# 32pinromtoflash.net
KiCad netlist of a schematic drawn in EAGLE
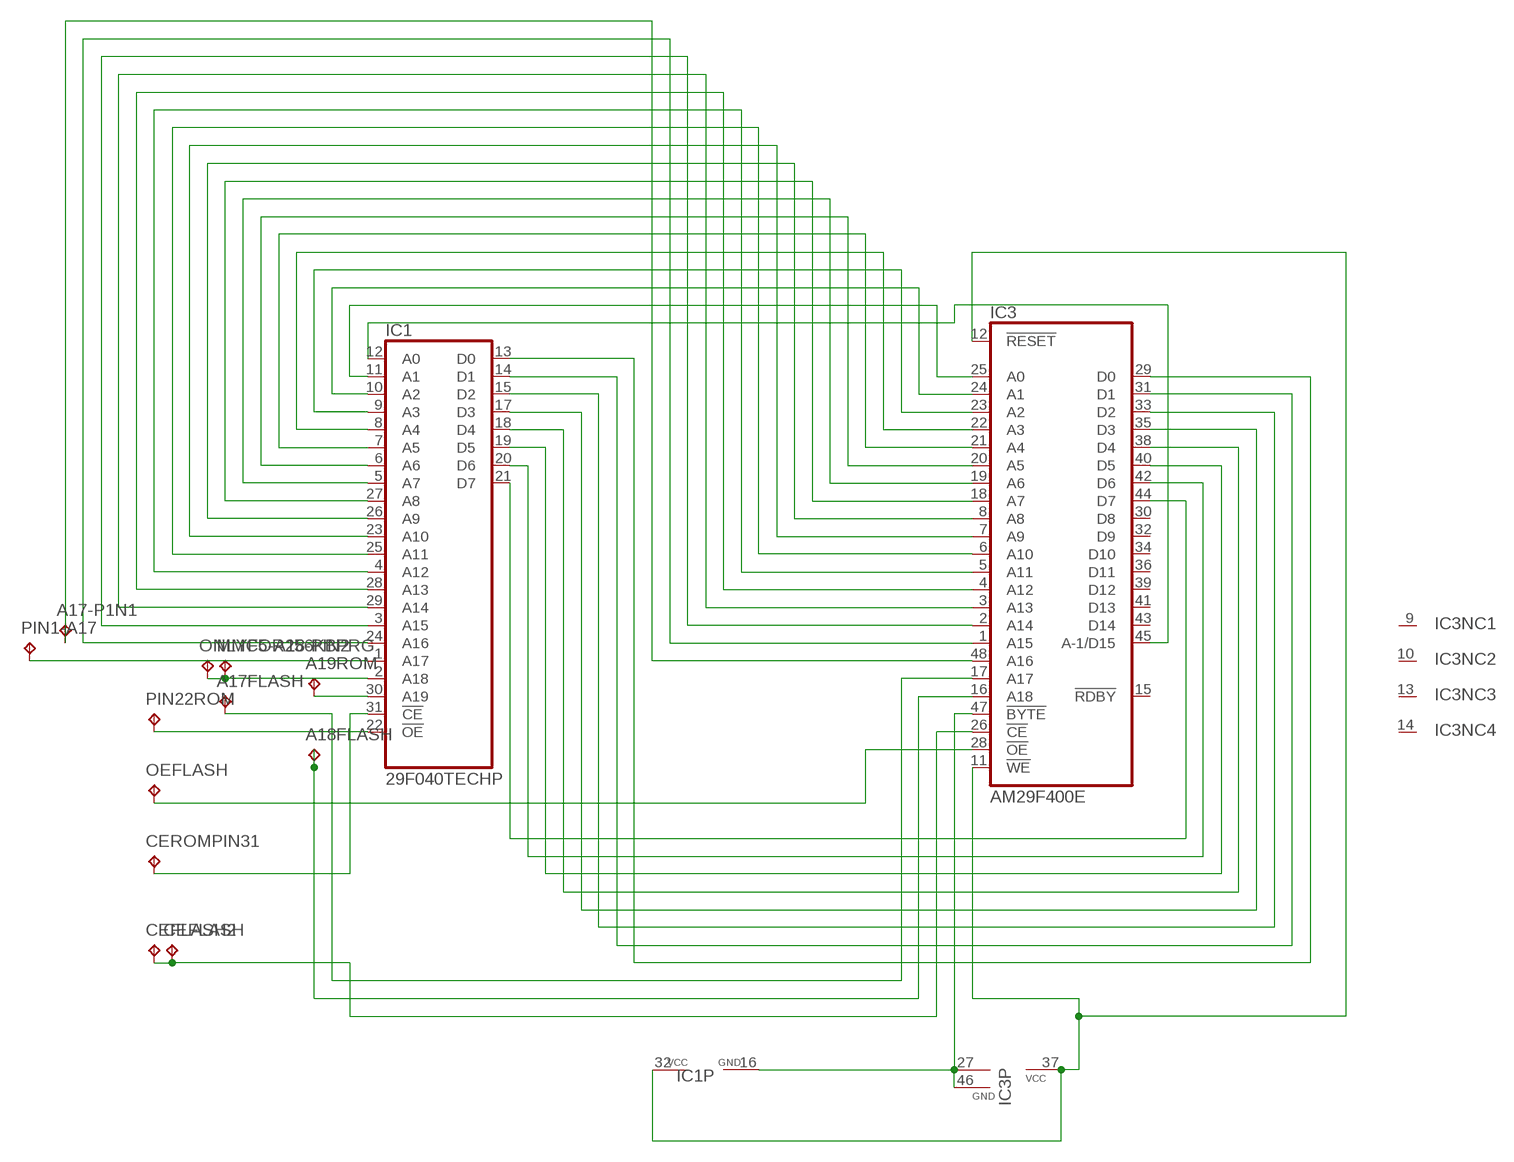
[diagram p0: schematic, sheet 1]

(export (version "E")
  (design (tool "Eeschema 10.0.6"))
  (components
    (comp (ref "A17-P1N1")
      (value "TPTP07SQ")
      (footprint "eagle-import:TP07SQ")
      (libsource (lib "eagle-import") (part "TPTP07SQ"))
    )
    (comp (ref "A17FLASH")
      (value "TPTP07SQ")
      (footprint "eagle-import:TP07SQ")
      (libsource (lib "eagle-import") (part "TPTP07SQ"))
    )
    (comp (ref "A18FLASH")
      (value "TPTP07SQ")
      (footprint "eagle-import:TP07SQ")
      (libsource (lib "eagle-import") (part "TPTP07SQ"))
    )
    (comp (ref "A19ROM")
      (value "TPTP07SQ")
      (footprint "eagle-import:TP07SQ")
      (libsource (lib "eagle-import") (part "TPTP07SQ"))
    )
    (comp (ref "CEFLASH")
      (value "TPTP07SQ")
      (footprint "eagle-import:TP07SQ")
      (libsource (lib "eagle-import") (part "TPTP07SQ"))
    )
    (comp (ref "CEFLASH2")
      (value "TPTP07SQ")
      (footprint "eagle-import:TP07SQ")
      (libsource (lib "eagle-import") (part "TPTP07SQ"))
    )
    (comp (ref "CEROMPIN31")
      (value "TPTP07SQ")
      (footprint "eagle-import:TP07SQ")
      (libsource (lib "eagle-import") (part "TPTP07SQ"))
    )
    (comp (ref "IC1")
      (value "29F040TECHP")
      (footprint "eagle-import:DIL32-3")
      (libsource (lib "eagle-import") (part "29F040PTECH"))
    )
    (comp (ref "IC3")
      (value "AM29F400E")
      (footprint "eagle-import:TSOP48")
      (libsource (lib "eagle-import") (part "AM29F400E"))
    )
    (comp (ref "MMC5-A18-PIN2")
      (value "TPTP07SQ")
      (footprint "eagle-import:TP07SQ")
      (libsource (lib "eagle-import") (part "TPTP07SQ"))
    )
    (comp (ref "OEFLASH")
      (value "TPTP07SQ")
      (footprint "eagle-import:TP07SQ")
      (libsource (lib "eagle-import") (part "TPTP07SQ"))
    )
    (comp (ref "ONLYFOR256KBPRG")
      (value "TPTP07SQ")
      (footprint "eagle-import:TP07SQ")
      (libsource (lib "eagle-import") (part "TPTP07SQ"))
    )
    (comp (ref "PIN1-A17")
      (value "TPTP07SQ")
      (footprint "eagle-import:TP07SQ")
      (libsource (lib "eagle-import") (part "TPTP07SQ"))
    )
    (comp (ref "PIN22ROM")
      (value "TPTP07SQ")
      (footprint "eagle-import:TP07SQ")
      (libsource (lib "eagle-import") (part "TPTP07SQ"))
    )
  )
  (nets
    (net (code "1") (name "Net-(IC1A-A0)") (class "Default")
      (node (ref "IC1") (pin "12") (pinfunction "A0_12") (pintype "input"))
      (node (ref "IC3") (pin "45") (pinfunction "A-1/D15_45") (pintype "tri_state"))
    )
    (net (code "2") (name "Net-(IC1A-A1)") (class "Default")
      (node (ref "IC1") (pin "11") (pinfunction "A1_11") (pintype "input"))
      (node (ref "IC3") (pin "25") (pinfunction "A0_25") (pintype "input"))
    )
    (net (code "3") (name "Net-(IC1A-A2)") (class "Default")
      (node (ref "IC1") (pin "10") (pinfunction "A2_10") (pintype "input"))
      (node (ref "IC3") (pin "24") (pinfunction "A1_24") (pintype "input"))
    )
    (net (code "4") (name "Net-(IC1A-A3)") (class "Default")
      (node (ref "IC1") (pin "9") (pinfunction "A3_9") (pintype "input"))
      (node (ref "IC3") (pin "23") (pinfunction "A2_23") (pintype "input"))
    )
    (net (code "5") (name "Net-(IC1A-A4)") (class "Default")
      (node (ref "IC1") (pin "8") (pinfunction "A4_8") (pintype "input"))
      (node (ref "IC3") (pin "22") (pinfunction "A3_22") (pintype "input"))
    )
    (net (code "6") (name "Net-(IC1A-A5)") (class "Default")
      (node (ref "IC1") (pin "7") (pinfunction "A5_7") (pintype "input"))
      (node (ref "IC3") (pin "21") (pinfunction "A4_21") (pintype "input"))
    )
    (net (code "7") (name "Net-(IC1A-A6)") (class "Default")
      (node (ref "IC1") (pin "6") (pinfunction "A6_6") (pintype "input"))
      (node (ref "IC3") (pin "20") (pinfunction "A5_20") (pintype "input"))
    )
    (net (code "8") (name "Net-(IC1A-A7)") (class "Default")
      (node (ref "IC1") (pin "5") (pinfunction "A7_5") (pintype "input"))
      (node (ref "IC3") (pin "19") (pinfunction "A6_19") (pintype "input"))
    )
    (net (code "9") (name "Net-(IC1A-A8)") (class "Default")
      (node (ref "IC1") (pin "27") (pinfunction "A8_27") (pintype "input"))
      (node (ref "IC3") (pin "18") (pinfunction "A7_18") (pintype "input"))
    )
    (net (code "10") (name "Net-(IC1A-A9)") (class "Default")
      (node (ref "IC1") (pin "26") (pinfunction "A9_26") (pintype "input"))
      (node (ref "IC3") (pin "8") (pinfunction "A8_8") (pintype "input"))
    )
    (net (code "11") (name "Net-(IC1A-A10)") (class "Default")
      (node (ref "IC1") (pin "23") (pinfunction "A10_23") (pintype "input"))
      (node (ref "IC3") (pin "7") (pinfunction "A9_7") (pintype "input"))
    )
    (net (code "12") (name "Net-(IC1A-A11)") (class "Default")
      (node (ref "IC1") (pin "25") (pinfunction "A11_25") (pintype "input"))
      (node (ref "IC3") (pin "6") (pinfunction "A10_6") (pintype "input"))
    )
    (net (code "13") (name "Net-(IC1A-A12)") (class "Default")
      (node (ref "IC1") (pin "4") (pinfunction "A12_4") (pintype "input"))
      (node (ref "IC3") (pin "5") (pinfunction "A11_5") (pintype "input"))
    )
    (net (code "14") (name "Net-(IC1A-A13)") (class "Default")
      (node (ref "IC1") (pin "28") (pinfunction "A13_28") (pintype "input"))
      (node (ref "IC3") (pin "4") (pinfunction "A12_4") (pintype "input"))
    )
    (net (code "15") (name "Net-(IC1A-A14)") (class "Default")
      (node (ref "IC1") (pin "29") (pinfunction "A14_29") (pintype "input"))
      (node (ref "IC3") (pin "3") (pinfunction "A13_3") (pintype "input"))
    )
    (net (code "16") (name "Net-(IC1A-A15)") (class "Default")
      (node (ref "IC1") (pin "3") (pinfunction "A15_3") (pintype "input"))
      (node (ref "IC3") (pin "2") (pinfunction "A14_2") (pintype "input"))
    )
    (net (code "17") (name "Net-(IC1A-A16)") (class "Default")
      (node (ref "IC1") (pin "24") (pinfunction "A16_24") (pintype "input"))
      (node (ref "IC3") (pin "1") (pinfunction "A15_1") (pintype "input"))
    )
    (net (code "18") (name "Net-(IC1A-A17)") (class "Default")
      (node (ref "IC1") (pin "1") (pinfunction "A17_1") (pintype "input"))
      (node (ref "PIN1-A17") (pin "TP") (pinfunction "TP_TP") (pintype "input"))
    )
    (net (code "19") (name "Net-(IC1A-A18)") (class "Default")
      (node (ref "IC1") (pin "2") (pinfunction "A18_2") (pintype "input"))
      (node (ref "MMC5-A18-PIN2") (pin "TP") (pinfunction "TP_TP") (pintype "input"))
      (node (ref "ONLYFOR256KBPRG") (pin "TP") (pinfunction "TP_TP") (pintype "input"))
    )
    (net (code "20") (name "Net-(IC1A-A19)") (class "Default")
      (node (ref "A19ROM") (pin "TP") (pinfunction "TP_TP") (pintype "input"))
      (node (ref "IC1") (pin "30") (pinfunction "A19_30") (pintype "input"))
    )
    (net (code "21") (name "Net-(IC1A-D0)") (class "Default")
      (node (ref "IC1") (pin "13") (pinfunction "D0_13") (pintype "tri_state"))
      (node (ref "IC3") (pin "29") (pinfunction "D0_29") (pintype "tri_state"))
    )
    (net (code "22") (name "Net-(IC1A-D1)") (class "Default")
      (node (ref "IC1") (pin "14") (pinfunction "D1_14") (pintype "tri_state"))
      (node (ref "IC3") (pin "31") (pinfunction "D1_31") (pintype "tri_state"))
    )
    (net (code "23") (name "Net-(IC1A-D2)") (class "Default")
      (node (ref "IC1") (pin "15") (pinfunction "D2_15") (pintype "tri_state"))
      (node (ref "IC3") (pin "33") (pinfunction "D2_33") (pintype "tri_state"))
    )
    (net (code "24") (name "Net-(IC1A-D3)") (class "Default")
      (node (ref "IC1") (pin "17") (pinfunction "D3_17") (pintype "tri_state"))
      (node (ref "IC3") (pin "35") (pinfunction "D3_35") (pintype "tri_state"))
    )
    (net (code "25") (name "Net-(IC1A-D4)") (class "Default")
      (node (ref "IC1") (pin "18") (pinfunction "D4_18") (pintype "tri_state"))
      (node (ref "IC3") (pin "38") (pinfunction "D4_38") (pintype "tri_state"))
    )
    (net (code "26") (name "Net-(IC1A-D5)") (class "Default")
      (node (ref "IC1") (pin "19") (pinfunction "D5_19") (pintype "tri_state"))
      (node (ref "IC3") (pin "40") (pinfunction "D5_40") (pintype "tri_state"))
    )
    (net (code "27") (name "Net-(IC1A-D6)") (class "Default")
      (node (ref "IC1") (pin "20") (pinfunction "D6_20") (pintype "tri_state"))
      (node (ref "IC3") (pin "42") (pinfunction "D6_42") (pintype "tri_state"))
    )
    (net (code "28") (name "Net-(IC1A-D7)") (class "Default")
      (node (ref "IC1") (pin "21") (pinfunction "D7_21") (pintype "input"))
      (node (ref "IC3") (pin "44") (pinfunction "D7_44") (pintype "tri_state"))
    )
    (net (code "29") (name "Net-(IC1A-~{CE})") (class "Default")
      (node (ref "CEROMPIN31") (pin "TP") (pinfunction "TP_TP") (pintype "input"))
      (node (ref "IC1") (pin "31") (pinfunction "~{CE}_31") (pintype "input"))
    )
    (net (code "30") (name "Net-(IC1A-~{OE})") (class "Default")
      (node (ref "IC1") (pin "22") (pinfunction "~{OE}_22") (pintype "input"))
      (node (ref "PIN22ROM") (pin "TP") (pinfunction "TP_TP") (pintype "input"))
    )
    (net (code "31") (name "Net-(IC1B-GND)") (class "Default")
      (node (ref "IC1") (pin "16") (pinfunction "GND_16") (pintype "power_in"))
      (node (ref "IC3") (pin "27") (pinfunction "GND_27") (pintype "power_in"))
      (node (ref "IC3") (pin "46") (pinfunction "GND_46") (pintype "power_in"))
      (node (ref "IC3") (pin "47") (pinfunction "~{BYTE}_47") (pintype "input"))
    )
    (net (code "32") (name "Net-(IC1B-VCC)") (class "Default")
      (node (ref "IC1") (pin "32") (pinfunction "VCC_32") (pintype "power_in"))
      (node (ref "IC3") (pin "11") (pinfunction "~{WE}_11") (pintype "input"))
      (node (ref "IC3") (pin "12") (pinfunction "~{RESET}_12") (pintype "input"))
      (node (ref "IC3") (pin "37") (pinfunction "VCC_37") (pintype "power_in"))
    )
    (net (code "33") (name "Net-(IC3A-A16)") (class "Default")
      (node (ref "A17-P1N1") (pin "TP") (pinfunction "TP_TP") (pintype "input"))
      (node (ref "IC3") (pin "48") (pinfunction "A16_48") (pintype "input"))
    )
    (net (code "34") (name "Net-(IC3A-A17)") (class "Default")
      (node (ref "A17FLASH") (pin "TP") (pinfunction "TP_TP") (pintype "input"))
      (node (ref "IC3") (pin "17") (pinfunction "A17_17") (pintype "input"))
    )
    (net (code "35") (name "Net-(IC3A-A18)") (class "Default")
      (node (ref "A18FLASH") (pin "TP") (pinfunction "TP_TP") (pintype "input"))
      (node (ref "IC3") (pin "16") (pinfunction "A18_16") (pintype "input"))
    )
    (net (code "36") (name "Net-(IC3A-~{CE})") (class "Default")
      (node (ref "CEFLASH") (pin "TP") (pinfunction "TP_TP") (pintype "input"))
      (node (ref "CEFLASH2") (pin "TP") (pinfunction "TP_TP") (pintype "input"))
      (node (ref "IC3") (pin "26") (pinfunction "~{CE}_26") (pintype "input"))
    )
    (net (code "37") (name "Net-(IC3A-~{OE})") (class "Default")
      (node (ref "IC3") (pin "28") (pinfunction "~{OE}_28") (pintype "input"))
      (node (ref "OEFLASH") (pin "TP") (pinfunction "TP_TP") (pintype "input"))
    )
    (net (code "38") (name "unconnected-(IC3A-D8-Pad30)") (class "Default")
      (node (ref "IC3") (pin "30") (pinfunction "D8_30") (pintype "tri_state"))
    )
    (net (code "39") (name "unconnected-(IC3A-D9-Pad32)") (class "Default")
      (node (ref "IC3") (pin "32") (pinfunction "D9_32") (pintype "tri_state"))
    )
    (net (code "40") (name "unconnected-(IC3A-D10-Pad34)") (class "Default")
      (node (ref "IC3") (pin "34") (pinfunction "D10_34") (pintype "tri_state"))
    )
    (net (code "41") (name "unconnected-(IC3A-D11-Pad36)") (class "Default")
      (node (ref "IC3") (pin "36") (pinfunction "D11_36") (pintype "tri_state"))
    )
    (net (code "42") (name "unconnected-(IC3A-D12-Pad39)") (class "Default")
      (node (ref "IC3") (pin "39") (pinfunction "D12_39") (pintype "tri_state"))
    )
    (net (code "43") (name "unconnected-(IC3A-D13-Pad41)") (class "Default")
      (node (ref "IC3") (pin "41") (pinfunction "D13_41") (pintype "tri_state"))
    )
    (net (code "44") (name "unconnected-(IC3A-D14-Pad43)") (class "Default")
      (node (ref "IC3") (pin "43") (pinfunction "D14_43") (pintype "tri_state"))
    )
    (net (code "45") (name "unconnected-(IC3A-~{RDBY}-Pad15)") (class "Default")
      (node (ref "IC3") (pin "15") (pinfunction "~{RDBY}_15") (pintype "output"))
    )
    (net (code "46") (name "unconnected-(IC3B-NC-Pad9)") (class "Default")
      (node (ref "IC3") (pin "9") (pinfunction "NC_9") (pintype "no_connect"))
    )
    (net (code "47") (name "unconnected-(IC3C-NC-Pad10)") (class "Default")
      (node (ref "IC3") (pin "10") (pinfunction "NC_10") (pintype "no_connect"))
    )
    (net (code "48") (name "unconnected-(IC3D-NC-Pad13)") (class "Default")
      (node (ref "IC3") (pin "13") (pinfunction "NC_13") (pintype "no_connect"))
    )
    (net (code "49") (name "unconnected-(IC3E-NC-Pad14)") (class "Default")
      (node (ref "IC3") (pin "14") (pinfunction "NC_14") (pintype "no_connect"))
    )
  )
)
